# Earphone-1.net
KiCad netlist of a schematic drawn in Altium Designer
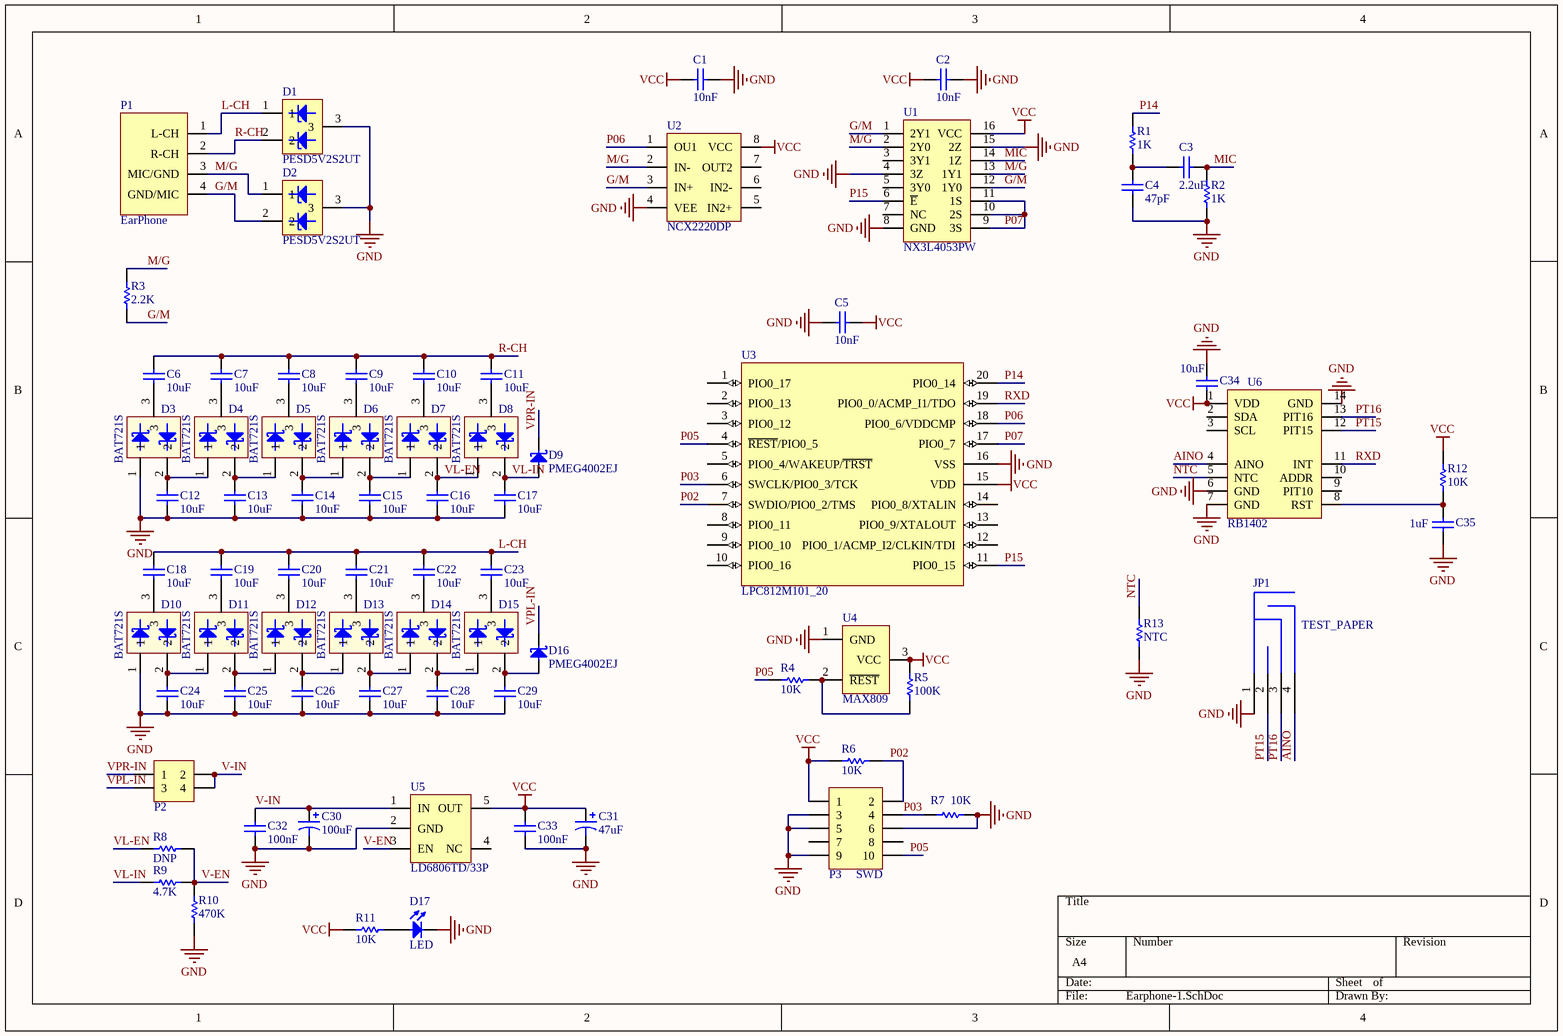
[diagram p0: Earphone-1.SchDoc]

(export (version "E")
  (design (tool "Eeschema 10.0.6"))
  (components
    (comp (ref "C1") (value "10nF") (footprint "0402C") (libsource (lib "Schlib1") (part "CAP")))
    (comp (ref "C2") (value "10nF") (footprint "0402C") (libsource (lib "Schlib1") (part "CAP")))
    (comp (ref "C3") (value "2.2uF") (footprint "0402C") (libsource (lib "Schlib1") (part "CAP")))
    (comp (ref "C4") (value "47pF") (footprint "0402C") (libsource (lib "Schlib1") (part "CAP")))
    (comp (ref "C5") (value "10nF") (footprint "0402C") (libsource (lib "Schlib1") (part "CAP")))
    (comp (ref "C6") (value "10uF") (footprint "0402C") (libsource (lib "Schlib1") (part "CAP")))
    (comp (ref "C7") (value "10uF") (footprint "0402C") (libsource (lib "Schlib1") (part "CAP")))
    (comp (ref "C8") (value "10uF") (footprint "0402C") (libsource (lib "Schlib1") (part "CAP")))
    (comp (ref "C9") (value "10uF") (footprint "0402C") (libsource (lib "Schlib1") (part "CAP")))
    (comp (ref "C10") (value "10uF") (footprint "0402C") (libsource (lib "Schlib1") (part "CAP")))
    (comp (ref "C11") (value "10uF") (footprint "0402C") (libsource (lib "Schlib1") (part "CAP")))
    (comp (ref "C12") (value "10uF") (footprint "0402C") (libsource (lib "Schlib1") (part "CAP")))
    (comp (ref "C13") (value "10uF") (footprint "0402C") (libsource (lib "Schlib1") (part "CAP")))
    (comp (ref "C14") (value "10uF") (footprint "0402C") (libsource (lib "Schlib1") (part "CAP")))
    (comp (ref "C15") (value "10uF") (footprint "0402C") (libsource (lib "Schlib1") (part "CAP")))
    (comp (ref "C16") (value "10uF") (footprint "0402C") (libsource (lib "Schlib1") (part "CAP")))
    (comp (ref "C17") (value "10uF") (footprint "0402C") (libsource (lib "Schlib1") (part "CAP")))
    (comp (ref "C18") (value "10uF") (footprint "0402C") (libsource (lib "Schlib1") (part "CAP")))
    (comp (ref "C19") (value "10uF") (footprint "0402C") (libsource (lib "Schlib1") (part "CAP")))
    (comp (ref "C20") (value "10uF") (footprint "0402C") (libsource (lib "Schlib1") (part "CAP")))
    (comp (ref "C21") (value "10uF") (footprint "0402C") (libsource (lib "Schlib1") (part "CAP")))
    (comp (ref "C22") (value "10uF") (footprint "0402C") (libsource (lib "Schlib1") (part "CAP")))
    (comp (ref "C23") (value "10uF") (footprint "0402C") (libsource (lib "Schlib1") (part "CAP")))
    (comp (ref "C24") (value "10uF") (footprint "0402C") (libsource (lib "Schlib1") (part "CAP")))
    (comp (ref "C25") (value "10uF") (footprint "0402C") (libsource (lib "Schlib1") (part "CAP")))
    (comp (ref "C26") (value "10uF") (footprint "0402C") (libsource (lib "Schlib1") (part "CAP")))
    (comp (ref "C27") (value "10uF") (footprint "0402C") (libsource (lib "Schlib1") (part "CAP")))
    (comp (ref "C28") (value "10uF") (footprint "0402C") (libsource (lib "Schlib1") (part "CAP")))
    (comp (ref "C29") (value "10uF") (footprint "0402C") (libsource (lib "Schlib1") (part "CAP")))
    (comp (ref "C30") (value "100uF") (footprint "T3216-18[A]") (libsource (lib "Schlib1") (part "CAP POL2")))
    (comp (ref "C31") (value "47uF") (footprint "T3216-18[A]") (libsource (lib "Schlib1") (part "CAP POL2")))
    (comp (ref "C32") (value "100nF") (footprint "0402C") (libsource (lib "Schlib1") (part "CAP")))
    (comp (ref "C33") (value "100nF") (footprint "0402C") (libsource (lib "Schlib1") (part "CAP")))
    (comp (ref "C34") (value "10uF") (footprint "0402C") (libsource (lib "Schlib1") (part "CAP")))
    (comp (ref "C35") (value "1uF") (footprint "0402C") (libsource (lib "Schlib1") (part "CAP")))
    (comp (ref "D1")
      (value "PESD5V2S2UT")
      (footprint "SOT23")
      (description "SOT23")
      (libsource (lib "Schlib1") (part "PESD5V2S2UT"))
    )
    (comp (ref "D2")
      (value "PESD5V2S2UT")
      (footprint "SOT23")
      (description "SOT23")
      (libsource (lib "Schlib1") (part "PESD5V2S2UT"))
    )
    (comp (ref "D3")
      (value "BAT721S")
      (footprint "SOT23")
      (description "SOT23")
      (libsource (lib "Schlib1") (part "BAT721S"))
    )
    (comp (ref "D4")
      (value "BAT721S")
      (footprint "SOT23")
      (description "SOT23")
      (libsource (lib "Schlib1") (part "BAT721S"))
    )
    (comp (ref "D5")
      (value "BAT721S")
      (footprint "SOT23")
      (description "SOT23")
      (libsource (lib "Schlib1") (part "BAT721S"))
    )
    (comp (ref "D6")
      (value "BAT721S")
      (footprint "SOT23")
      (description "SOT23")
      (libsource (lib "Schlib1") (part "BAT721S"))
    )
    (comp (ref "D7")
      (value "BAT721S")
      (footprint "SOT23")
      (description "SOT23")
      (libsource (lib "Schlib1") (part "BAT721S"))
    )
    (comp (ref "D8")
      (value "BAT721S")
      (footprint "SOT23")
      (description "SOT23")
      (libsource (lib "Schlib1") (part "BAT721S"))
    )
    (comp (ref "D9")
      (value "PMEG4002EJ")
      (footprint "SOD323")
      (description "SOD323F")
      (libsource (lib "Schlib1") (part "PMEG4002EJ"))
    )
    (comp (ref "D10")
      (value "BAT721S")
      (footprint "SOT23")
      (description "SOT23")
      (libsource (lib "Schlib1") (part "BAT721S"))
    )
    (comp (ref "D11")
      (value "BAT721S")
      (footprint "SOT23")
      (description "SOT23")
      (libsource (lib "Schlib1") (part "BAT721S"))
    )
    (comp (ref "D12")
      (value "BAT721S")
      (footprint "SOT23")
      (description "SOT23")
      (libsource (lib "Schlib1") (part "BAT721S"))
    )
    (comp (ref "D13")
      (value "BAT721S")
      (footprint "SOT23")
      (description "SOT23")
      (libsource (lib "Schlib1") (part "BAT721S"))
    )
    (comp (ref "D14")
      (value "BAT721S")
      (footprint "SOT23")
      (description "SOT23")
      (libsource (lib "Schlib1") (part "BAT721S"))
    )
    (comp (ref "D15")
      (value "BAT721S")
      (footprint "SOT23")
      (description "SOT23")
      (libsource (lib "Schlib1") (part "BAT721S"))
    )
    (comp (ref "D16")
      (value "PMEG4002EJ")
      (footprint "SOD323")
      (description "SOD323F")
      (libsource (lib "Schlib1") (part "PMEG4002EJ"))
    )
    (comp (ref "D17") (value "LED") (footprint "0603L") (libsource (lib "Schlib1") (part "LED")))
    (comp (ref "JP1")
      (value "TEST_PAPER")
      (footprint "TEST_PAPER")
      (libsource (lib "Schlib1") (part "TEST_PAPER"))
    )
    (comp (ref "P1") (value "EarPhone") (footprint "EarPhone") (libsource (lib "Schlib1") (part "EarPhone")))
    (comp (ref "P2")
      (value "Header-2X2")
      (footprint "header-2x2(2.54)")
      (libsource (lib "Schlib1") (part "Header-2X2"))
    )
    (comp (ref "P3")
      (value "SWD")
      (footprint "header-2x5(2.54)")
      (libsource (lib "Schlib1") (part "Header-2X5"))
    )
    (comp (ref "R1") (value "1K") (footprint "0402R") (libsource (lib "Schlib1") (part "RES")))
    (comp (ref "R2") (value "1K") (footprint "0402R") (libsource (lib "Schlib1") (part "RES")))
    (comp (ref "R3") (value "2.2K") (footprint "0402R") (libsource (lib "Schlib1") (part "RES")))
    (comp (ref "R4") (value "10K") (footprint "0402R") (libsource (lib "Schlib1") (part "RES")))
    (comp (ref "R5") (value "100K") (footprint "0402R") (libsource (lib "Schlib1") (part "RES")))
    (comp (ref "R6") (value "10K") (footprint "0402R") (libsource (lib "Schlib1") (part "RES")))
    (comp (ref "R7") (value "10K") (footprint "0402R") (libsource (lib "Schlib1") (part "RES")))
    (comp (ref "R8") (value "DNP") (footprint "0402R") (libsource (lib "Schlib1") (part "RES")))
    (comp (ref "R9") (value "4.7K") (footprint "0402R") (libsource (lib "Schlib1") (part "RES")))
    (comp (ref "R10") (value "470K") (footprint "0402R") (libsource (lib "Schlib1") (part "RES")))
    (comp (ref "R11") (value "10K") (footprint "0402R") (libsource (lib "Schlib1") (part "RES")))
    (comp (ref "R12") (value "10K") (footprint "0402R") (libsource (lib "Schlib1") (part "RES")))
    (comp (ref "R13") (value "NTC") (footprint "0603R") (libsource (lib "Schlib1") (part "RES")))
    (comp (ref "U1")
      (value "NX3L4053PW")
      (footprint "TSSOP16")
      (description "TSSOP16(SOT403-1)")
      (libsource (lib "Schlib1") (part "NX3L4053PW"))
    )
    (comp (ref "U2")
      (value "NCX2220DP")
      (footprint "TSSOP8")
      (description "TSSOP8(SOT505-2)")
      (libsource (lib "Schlib1") (part "NCX2220DP"))
    )
    (comp (ref "U3")
      (value "LPC812M101_20")
      (footprint "TSSOP20")
      (description "TSSOP20")
      (libsource (lib "Schlib1") (part "LPC812M101_20"))
    )
    (comp (ref "U4")
      (value "MAX809")
      (footprint "SOT23")
      (description "SOT23")
      (libsource (lib "Schlib1") (part "MAX809"))
    )
    (comp (ref "U5")
      (value "LD6806TD/33P")
      (footprint "SOT753 (TSOP5)")
      (description "TSOP5(SOT753)")
      (libsource (lib "Schlib1") (part "LD6806TD/33P"))
    )
    (comp (ref "U6") (value "RB1402") (footprint "RB1402") (libsource (lib "Schlib1") (part "RB1402")))
  )
  (nets
    (net (code "1") (name "/AINO") (class "Default")
      (node (ref "JP1") (pin "4") (pinfunction "P_4") (pintype "passive"))
      (node (ref "U6") (pin "4") (pinfunction "AINO_4") (pintype "passive"))
    )
    (net (code "2") (name "/G{slash}M") (class "Default")
      (node (ref "D2") (pin "2") (pinfunction "2_2") (pintype "passive"))
      (node (ref "P1") (pin "4") (pinfunction "GND/MIC_4") (pintype "passive"))
      (node (ref "R3") (pin "1") (pinfunction "1_1") (pintype "passive"))
      (node (ref "U1") (pin "1") (pinfunction "2Y1_1") (pintype "passive"))
      (node (ref "U1") (pin "12") (pinfunction "1Y0_12") (pintype "passive"))
      (node (ref "U2") (pin "3") (pinfunction "IN+_3") (pintype "passive"))
    )
    (net (code "3") (name "/L-CH") (class "Default")
      (node (ref "C18") (pin "2") (pinfunction "2_2") (pintype "passive"))
      (node (ref "C19") (pin "2") (pinfunction "2_2") (pintype "passive"))
      (node (ref "C20") (pin "2") (pinfunction "2_2") (pintype "passive"))
      (node (ref "C21") (pin "2") (pinfunction "2_2") (pintype "passive"))
      (node (ref "C22") (pin "2") (pinfunction "2_2") (pintype "passive"))
      (node (ref "C23") (pin "2") (pinfunction "2_2") (pintype "passive"))
      (node (ref "D1") (pin "1") (pinfunction "1_1") (pintype "passive"))
      (node (ref "P1") (pin "1") (pinfunction "L-CH_1") (pintype "passive"))
    )
    (net (code "4") (name "/MIC") (class "Default")
      (node (ref "C3") (pin "1") (pinfunction "1_1") (pintype "passive"))
      (node (ref "R2") (pin "1") (pinfunction "1_1") (pintype "passive"))
      (node (ref "U1") (pin "14") (pinfunction "1Z_14") (pintype "passive"))
    )
    (net (code "5") (name "/M{slash}G") (class "Default")
      (node (ref "D2") (pin "1") (pinfunction "1_1") (pintype "passive"))
      (node (ref "P1") (pin "3") (pinfunction "MIC/GND_3") (pintype "passive"))
      (node (ref "R3") (pin "2") (pinfunction "2_2") (pintype "passive"))
      (node (ref "U1") (pin "13") (pinfunction "1Y1_13") (pintype "passive"))
      (node (ref "U1") (pin "2") (pinfunction "2Y0_2") (pintype "passive"))
      (node (ref "U2") (pin "2") (pinfunction "IN-_2") (pintype "passive"))
    )
    (net (code "6") (name "/NTC") (class "Default")
      (node (ref "R13") (pin "2") (pinfunction "2_2") (pintype "passive"))
      (node (ref "U6") (pin "5") (pinfunction "NTC_5") (pintype "passive"))
    )
    (net (code "7") (name "/P02") (class "Default")
      (node (ref "P3") (pin "2") (pinfunction "2_2") (pintype "passive"))
      (node (ref "R6") (pin "2") (pinfunction "2_2") (pintype "passive"))
      (node (ref "U3") (pin "7") (pinfunction "SWDIO/PIO0_2/TMS_7") (pintype "bidirectional"))
    )
    (net (code "8") (name "/P03") (class "Default")
      (node (ref "P3") (pin "4") (pinfunction "4_4") (pintype "passive"))
      (node (ref "R7") (pin "1") (pinfunction "1_1") (pintype "passive"))
      (node (ref "U3") (pin "6") (pinfunction "SWCLK/PIO0_3/TCK_6") (pintype "bidirectional"))
    )
    (net (code "9") (name "/P05") (class "Default")
      (node (ref "P3") (pin "10") (pinfunction "10_10") (pintype "passive"))
      (node (ref "R4") (pin "1") (pinfunction "1_1") (pintype "passive"))
      (node (ref "U3") (pin "4") (pinfunction "~{REST}/PIO0_5_4") (pintype "bidirectional"))
    )
    (net (code "10") (name "/P06") (class "Default")
      (node (ref "U2") (pin "1") (pinfunction "OU1_1") (pintype "passive"))
      (node (ref "U3") (pin "18") (pinfunction "PIO0_6/VDDCMP_18") (pintype "bidirectional"))
    )
    (net (code "11") (name "/P07") (class "Default")
      (node (ref "U1") (pin "10") (pinfunction "2S_10") (pintype "passive"))
      (node (ref "U1") (pin "11") (pinfunction "1S_11") (pintype "passive"))
      (node (ref "U1") (pin "9") (pinfunction "3S_9") (pintype "passive"))
      (node (ref "U3") (pin "17") (pinfunction "PIO0_7_17") (pintype "bidirectional"))
    )
    (net (code "12") (name "/P14") (class "Default")
      (node (ref "R1") (pin "1") (pinfunction "1_1") (pintype "passive"))
      (node (ref "U3") (pin "20") (pinfunction "PIO0_14_20") (pintype "bidirectional"))
    )
    (net (code "13") (name "/P15") (class "Default")
      (node (ref "U1") (pin "6") (pinfunction "~{E}_6") (pintype "passive"))
      (node (ref "U3") (pin "11") (pinfunction "PIO0_15_11") (pintype "bidirectional"))
    )
    (net (code "14") (name "/PT15") (class "Default")
      (node (ref "JP1") (pin "2") (pinfunction "PC10_2") (pintype "passive"))
      (node (ref "U6") (pin "12") (pinfunction "PIT15_12") (pintype "passive"))
    )
    (net (code "15") (name "/PT16") (class "Default")
      (node (ref "JP1") (pin "3") (pinfunction "NOP_3") (pintype "passive"))
      (node (ref "U6") (pin "13") (pinfunction "PIT16_13") (pintype "passive"))
    )
    (net (code "16") (name "/R-CH") (class "Default")
      (node (ref "C10") (pin "2") (pinfunction "2_2") (pintype "passive"))
      (node (ref "C11") (pin "2") (pinfunction "2_2") (pintype "passive"))
      (node (ref "C6") (pin "2") (pinfunction "2_2") (pintype "passive"))
      (node (ref "C7") (pin "2") (pinfunction "2_2") (pintype "passive"))
      (node (ref "C8") (pin "2") (pinfunction "2_2") (pintype "passive"))
      (node (ref "C9") (pin "2") (pinfunction "2_2") (pintype "passive"))
      (node (ref "D1") (pin "2") (pinfunction "2_2") (pintype "passive"))
      (node (ref "P1") (pin "2") (pinfunction "R-CH_2") (pintype "passive"))
    )
    (net (code "17") (name "/RXD") (class "Default")
      (node (ref "U3") (pin "19") (pinfunction "PIO0_0/ACMP_I1/TDO_19") (pintype "bidirectional"))
      (node (ref "U6") (pin "11") (pinfunction "INT_11") (pintype "passive"))
    )
    (net (code "18") (name "/V-EN") (class "Default")
      (node (ref "R10") (pin "2") (pinfunction "2_2") (pintype "passive"))
      (node (ref "R8") (pin "2") (pinfunction "2_2") (pintype "passive"))
      (node (ref "R9") (pin "2") (pinfunction "2_2") (pintype "passive"))
      (node (ref "U5") (pin "3") (pinfunction "EN_3") (pintype "passive"))
    )
    (net (code "19") (name "/V-IN") (class "Default")
      (node (ref "C30") (pin "1") (pinfunction "1_1") (pintype "passive"))
      (node (ref "C32") (pin "2") (pinfunction "2_2") (pintype "passive"))
      (node (ref "P2") (pin "2") (pinfunction "2_2") (pintype "passive"))
      (node (ref "P2") (pin "4") (pinfunction "4_4") (pintype "passive"))
      (node (ref "U5") (pin "1") (pinfunction "IN_1") (pintype "passive"))
    )
    (net (code "20") (name "/VL-EN") (class "Default")
      (node (ref "C16") (pin "2") (pinfunction "2_2") (pintype "passive"))
      (node (ref "D7") (pin "2") (pinfunction "2_2") (pintype "passive"))
      (node (ref "D8") (pin "1") (pinfunction "1_1") (pintype "passive"))
      (node (ref "R8") (pin "1") (pinfunction "1_1") (pintype "passive"))
    )
    (net (code "21") (name "/VL-IN") (class "Default")
      (node (ref "C17") (pin "2") (pinfunction "2_2") (pintype "passive"))
      (node (ref "D8") (pin "2") (pinfunction "2_2") (pintype "passive"))
      (node (ref "D9") (pin "2") (pinfunction "2_2") (pintype "passive"))
      (node (ref "R9") (pin "1") (pinfunction "1_1") (pintype "passive"))
    )
    (net (code "22") (name "/VPL-IN") (class "Default")
      (node (ref "D16") (pin "1") (pinfunction "1_1") (pintype "passive"))
      (node (ref "P2") (pin "3") (pinfunction "3_3") (pintype "passive"))
    )
    (net (code "23") (name "/VPR-IN") (class "Default")
      (node (ref "D9") (pin "1") (pinfunction "1_1") (pintype "passive"))
      (node (ref "P2") (pin "1") (pinfunction "1_1") (pintype "passive"))
    )
    (net (code "24") (name "GND") (class "Default")
      (node (ref "C1") (pin "1") (pinfunction "1_1") (pintype "passive"))
      (node (ref "C12") (pin "1") (pinfunction "1_1") (pintype "passive"))
      (node (ref "C13") (pin "1") (pinfunction "1_1") (pintype "passive"))
      (node (ref "C14") (pin "1") (pinfunction "1_1") (pintype "passive"))
      (node (ref "C15") (pin "1") (pinfunction "1_1") (pintype "passive"))
      (node (ref "C16") (pin "1") (pinfunction "1_1") (pintype "passive"))
      (node (ref "C17") (pin "1") (pinfunction "1_1") (pintype "passive"))
      (node (ref "C2") (pin "2") (pinfunction "2_2") (pintype "passive"))
      (node (ref "C24") (pin "1") (pinfunction "1_1") (pintype "passive"))
      (node (ref "C25") (pin "1") (pinfunction "1_1") (pintype "passive"))
      (node (ref "C26") (pin "1") (pinfunction "1_1") (pintype "passive"))
      (node (ref "C27") (pin "1") (pinfunction "1_1") (pintype "passive"))
      (node (ref "C28") (pin "1") (pinfunction "1_1") (pintype "passive"))
      (node (ref "C29") (pin "1") (pinfunction "1_1") (pintype "passive"))
      (node (ref "C30") (pin "2") (pinfunction "2_2") (pintype "passive"))
      (node (ref "C31") (pin "2") (pinfunction "2_2") (pintype "passive"))
      (node (ref "C32") (pin "1") (pinfunction "1_1") (pintype "passive"))
      (node (ref "C33") (pin "1") (pinfunction "1_1") (pintype "passive"))
      (node (ref "C34") (pin "2") (pinfunction "2_2") (pintype "passive"))
      (node (ref "C35") (pin "1") (pinfunction "1_1") (pintype "passive"))
      (node (ref "C4") (pin "1") (pinfunction "1_1") (pintype "passive"))
      (node (ref "C5") (pin "1") (pinfunction "1_1") (pintype "passive"))
      (node (ref "D1") (pin "3") (pinfunction "3_3") (pintype "passive"))
      (node (ref "D10") (pin "1") (pinfunction "1_1") (pintype "passive"))
      (node (ref "D17") (pin "2") (pinfunction "K_2") (pintype "passive"))
      (node (ref "D2") (pin "3") (pinfunction "3_3") (pintype "passive"))
      (node (ref "D3") (pin "1") (pinfunction "1_1") (pintype "passive"))
      (node (ref "JP1") (pin "1") (pinfunction "N_1") (pintype "passive"))
      (node (ref "P3") (pin "3") (pinfunction "3_3") (pintype "passive"))
      (node (ref "P3") (pin "5") (pinfunction "5_5") (pintype "passive"))
      (node (ref "P3") (pin "6") (pinfunction "6_6") (pintype "passive"))
      (node (ref "P3") (pin "9") (pinfunction "9_9") (pintype "passive"))
      (node (ref "R10") (pin "1") (pinfunction "1_1") (pintype "passive"))
      (node (ref "R13") (pin "1") (pinfunction "1_1") (pintype "passive"))
      (node (ref "R2") (pin "2") (pinfunction "2_2") (pintype "passive"))
      (node (ref "R7") (pin "2") (pinfunction "2_2") (pintype "passive"))
      (node (ref "U1") (pin "15") (pinfunction "2Z_15") (pintype "passive"))
      (node (ref "U1") (pin "4") (pinfunction "3Z_4") (pintype "passive"))
      (node (ref "U1") (pin "8") (pinfunction "GND_8") (pintype "passive"))
      (node (ref "U2") (pin "4") (pinfunction "VEE_4") (pintype "passive"))
      (node (ref "U3") (pin "16") (pinfunction "VSS_16") (pintype "passive"))
      (node (ref "U4") (pin "1") (pinfunction "GND_1") (pintype "passive"))
      (node (ref "U5") (pin "2") (pinfunction "GND_2") (pintype "passive"))
      (node (ref "U6") (pin "14") (pinfunction "GND_14") (pintype "passive"))
      (node (ref "U6") (pin "6") (pinfunction "GND_6") (pintype "passive"))
      (node (ref "U6") (pin "7") (pinfunction "GND_7") (pintype "passive"))
    )
    (net (code "25") (name "Net-(C3-Pad2)") (class "Default")
      (node (ref "C3") (pin "2") (pinfunction "2_2") (pintype "passive"))
      (node (ref "C4") (pin "2") (pinfunction "2_2") (pintype "passive"))
      (node (ref "R1") (pin "2") (pinfunction "2_2") (pintype "passive"))
    )
    (net (code "26") (name "Net-(C6-Pad1)") (class "Default")
      (node (ref "C6") (pin "1") (pinfunction "1_1") (pintype "passive"))
      (node (ref "D3") (pin "3") (pinfunction "3_3") (pintype "passive"))
    )
    (net (code "27") (name "Net-(C7-Pad1)") (class "Default")
      (node (ref "C7") (pin "1") (pinfunction "1_1") (pintype "passive"))
      (node (ref "D4") (pin "3") (pinfunction "3_3") (pintype "passive"))
    )
    (net (code "28") (name "Net-(C8-Pad1)") (class "Default")
      (node (ref "C8") (pin "1") (pinfunction "1_1") (pintype "passive"))
      (node (ref "D5") (pin "3") (pinfunction "3_3") (pintype "passive"))
    )
    (net (code "29") (name "Net-(C9-Pad1)") (class "Default")
      (node (ref "C9") (pin "1") (pinfunction "1_1") (pintype "passive"))
      (node (ref "D6") (pin "3") (pinfunction "3_3") (pintype "passive"))
    )
    (net (code "30") (name "Net-(C10-Pad1)") (class "Default")
      (node (ref "C10") (pin "1") (pinfunction "1_1") (pintype "passive"))
      (node (ref "D7") (pin "3") (pinfunction "3_3") (pintype "passive"))
    )
    (net (code "31") (name "Net-(C11-Pad1)") (class "Default")
      (node (ref "C11") (pin "1") (pinfunction "1_1") (pintype "passive"))
      (node (ref "D8") (pin "3") (pinfunction "3_3") (pintype "passive"))
    )
    (net (code "32") (name "Net-(C12-Pad2)") (class "Default")
      (node (ref "C12") (pin "2") (pinfunction "2_2") (pintype "passive"))
      (node (ref "D3") (pin "2") (pinfunction "2_2") (pintype "passive"))
      (node (ref "D4") (pin "1") (pinfunction "1_1") (pintype "passive"))
    )
    (net (code "33") (name "Net-(C13-Pad2)") (class "Default")
      (node (ref "C13") (pin "2") (pinfunction "2_2") (pintype "passive"))
      (node (ref "D4") (pin "2") (pinfunction "2_2") (pintype "passive"))
      (node (ref "D5") (pin "1") (pinfunction "1_1") (pintype "passive"))
    )
    (net (code "34") (name "Net-(C14-Pad2)") (class "Default")
      (node (ref "C14") (pin "2") (pinfunction "2_2") (pintype "passive"))
      (node (ref "D5") (pin "2") (pinfunction "2_2") (pintype "passive"))
      (node (ref "D6") (pin "1") (pinfunction "1_1") (pintype "passive"))
    )
    (net (code "35") (name "Net-(C15-Pad2)") (class "Default")
      (node (ref "C15") (pin "2") (pinfunction "2_2") (pintype "passive"))
      (node (ref "D6") (pin "2") (pinfunction "2_2") (pintype "passive"))
      (node (ref "D7") (pin "1") (pinfunction "1_1") (pintype "passive"))
    )
    (net (code "36") (name "Net-(C18-Pad1)") (class "Default")
      (node (ref "C18") (pin "1") (pinfunction "1_1") (pintype "passive"))
      (node (ref "D10") (pin "3") (pinfunction "3_3") (pintype "passive"))
    )
    (net (code "37") (name "Net-(C19-Pad1)") (class "Default")
      (node (ref "C19") (pin "1") (pinfunction "1_1") (pintype "passive"))
      (node (ref "D11") (pin "3") (pinfunction "3_3") (pintype "passive"))
    )
    (net (code "38") (name "Net-(C20-Pad1)") (class "Default")
      (node (ref "C20") (pin "1") (pinfunction "1_1") (pintype "passive"))
      (node (ref "D12") (pin "3") (pinfunction "3_3") (pintype "passive"))
    )
    (net (code "39") (name "Net-(C21-Pad1)") (class "Default")
      (node (ref "C21") (pin "1") (pinfunction "1_1") (pintype "passive"))
      (node (ref "D13") (pin "3") (pinfunction "3_3") (pintype "passive"))
    )
    (net (code "40") (name "Net-(C22-Pad1)") (class "Default")
      (node (ref "C22") (pin "1") (pinfunction "1_1") (pintype "passive"))
      (node (ref "D14") (pin "3") (pinfunction "3_3") (pintype "passive"))
    )
    (net (code "41") (name "Net-(C23-Pad1)") (class "Default")
      (node (ref "C23") (pin "1") (pinfunction "1_1") (pintype "passive"))
      (node (ref "D15") (pin "3") (pinfunction "3_3") (pintype "passive"))
    )
    (net (code "42") (name "Net-(C24-Pad2)") (class "Default")
      (node (ref "C24") (pin "2") (pinfunction "2_2") (pintype "passive"))
      (node (ref "D10") (pin "2") (pinfunction "2_2") (pintype "passive"))
      (node (ref "D11") (pin "1") (pinfunction "1_1") (pintype "passive"))
    )
    (net (code "43") (name "Net-(C25-Pad2)") (class "Default")
      (node (ref "C25") (pin "2") (pinfunction "2_2") (pintype "passive"))
      (node (ref "D11") (pin "2") (pinfunction "2_2") (pintype "passive"))
      (node (ref "D12") (pin "1") (pinfunction "1_1") (pintype "passive"))
    )
    (net (code "44") (name "Net-(C26-Pad2)") (class "Default")
      (node (ref "C26") (pin "2") (pinfunction "2_2") (pintype "passive"))
      (node (ref "D12") (pin "2") (pinfunction "2_2") (pintype "passive"))
      (node (ref "D13") (pin "1") (pinfunction "1_1") (pintype "passive"))
    )
    (net (code "45") (name "Net-(C27-Pad2)") (class "Default")
      (node (ref "C27") (pin "2") (pinfunction "2_2") (pintype "passive"))
      (node (ref "D13") (pin "2") (pinfunction "2_2") (pintype "passive"))
      (node (ref "D14") (pin "1") (pinfunction "1_1") (pintype "passive"))
    )
    (net (code "46") (name "Net-(C28-Pad2)") (class "Default")
      (node (ref "C28") (pin "2") (pinfunction "2_2") (pintype "passive"))
      (node (ref "D14") (pin "2") (pinfunction "2_2") (pintype "passive"))
      (node (ref "D15") (pin "1") (pinfunction "1_1") (pintype "passive"))
    )
    (net (code "47") (name "Net-(C29-Pad2)") (class "Default")
      (node (ref "C29") (pin "2") (pinfunction "2_2") (pintype "passive"))
      (node (ref "D15") (pin "2") (pinfunction "2_2") (pintype "passive"))
      (node (ref "D16") (pin "2") (pinfunction "2_2") (pintype "passive"))
    )
    (net (code "48") (name "Net-(D17-A)") (class "Default")
      (node (ref "D17") (pin "1") (pinfunction "A_1") (pintype "passive"))
      (node (ref "R11") (pin "2") (pinfunction "2_2") (pintype "passive"))
    )
    (net (code "49") (name "Net-(U4-~{REST})") (class "Default")
      (node (ref "R4") (pin "2") (pinfunction "2_2") (pintype "passive"))
      (node (ref "R5") (pin "1") (pinfunction "1_1") (pintype "passive"))
      (node (ref "U4") (pin "2") (pinfunction "~{REST}_2") (pintype "passive"))
    )
    (net (code "50") (name "Net-(U6-RST)") (class "Default")
      (node (ref "C35") (pin "2") (pinfunction "2_2") (pintype "passive"))
      (node (ref "R12") (pin "1") (pinfunction "1_1") (pintype "passive"))
      (node (ref "U6") (pin "8") (pinfunction "RST_8") (pintype "passive"))
    )
    (net (code "51") (name "VCC") (class "Default")
      (node (ref "C1") (pin "2") (pinfunction "2_2") (pintype "passive"))
      (node (ref "C2") (pin "1") (pinfunction "1_1") (pintype "passive"))
      (node (ref "C31") (pin "1") (pinfunction "1_1") (pintype "passive"))
      (node (ref "C33") (pin "2") (pinfunction "2_2") (pintype "passive"))
      (node (ref "C34") (pin "1") (pinfunction "1_1") (pintype "passive"))
      (node (ref "C5") (pin "2") (pinfunction "2_2") (pintype "passive"))
      (node (ref "P3") (pin "1") (pinfunction "1_1") (pintype "passive"))
      (node (ref "R11") (pin "1") (pinfunction "1_1") (pintype "passive"))
      (node (ref "R12") (pin "2") (pinfunction "2_2") (pintype "passive"))
      (node (ref "R5") (pin "2") (pinfunction "2_2") (pintype "passive"))
      (node (ref "R6") (pin "1") (pinfunction "1_1") (pintype "passive"))
      (node (ref "U1") (pin "16") (pinfunction "VCC_16") (pintype "passive"))
      (node (ref "U2") (pin "8") (pinfunction "VCC_8") (pintype "passive"))
      (node (ref "U3") (pin "15") (pinfunction "VDD_15") (pintype "passive"))
      (node (ref "U4") (pin "3") (pinfunction "VCC_3") (pintype "passive"))
      (node (ref "U5") (pin "5") (pinfunction "OUT_5") (pintype "passive"))
      (node (ref "U6") (pin "1") (pinfunction "VDD_1") (pintype "passive"))
    )
    (net (code "52") (name "unconnected-(P3-Pad7)") (class "Default")
      (node (ref "P3") (pin "7") (pinfunction "7_7") (pintype "passive"))
    )
    (net (code "53") (name "unconnected-(P3-Pad8)") (class "Default")
      (node (ref "P3") (pin "8") (pinfunction "8_8") (pintype "passive"))
    )
    (net (code "54") (name "unconnected-(U1-3Y0-Pad5)") (class "Default")
      (node (ref "U1") (pin "5") (pinfunction "3Y0_5") (pintype "passive"))
    )
    (net (code "55") (name "unconnected-(U1-3Y1-Pad3)") (class "Default")
      (node (ref "U1") (pin "3") (pinfunction "3Y1_3") (pintype "passive"))
    )
    (net (code "56") (name "unconnected-(U1-NC-Pad7)") (class "Default")
      (node (ref "U1") (pin "7") (pinfunction "NC_7") (pintype "passive"))
    )
    (net (code "57") (name "unconnected-(U2-IN2+-Pad5)") (class "Default")
      (node (ref "U2") (pin "5") (pinfunction "IN2+_5") (pintype "passive"))
    )
    (net (code "58") (name "unconnected-(U2-IN2--Pad6)") (class "Default")
      (node (ref "U2") (pin "6") (pinfunction "IN2-_6") (pintype "passive"))
    )
    (net (code "59") (name "unconnected-(U2-OUT2-Pad7)") (class "Default")
      (node (ref "U2") (pin "7") (pinfunction "OUT2_7") (pintype "passive"))
    )
    (net (code "60") (name "unconnected-(U3-PIO0_1{slash}ACMP_I2{slash}CLKIN{slash}TDI-Pad12)") (class "Default")
      (node (ref "U3") (pin "12") (pinfunction "PIO0_1/ACMP_I2/CLKIN/TDI_12") (pintype "bidirectional"))
    )
    (net (code "61") (name "unconnected-(U3-PIO0_4{slash}WAKEUP{slash}~{TRST}-Pad5)") (class "Default")
      (node (ref "U3") (pin "5") (pinfunction "PIO0_4/WAKEUP/~{TRST}_5") (pintype "bidirectional"))
    )
    (net (code "62") (name "unconnected-(U3-PIO0_8{slash}XTALIN-Pad14)") (class "Default")
      (node (ref "U3") (pin "14") (pinfunction "PIO0_8/XTALIN_14") (pintype "bidirectional"))
    )
    (net (code "63") (name "unconnected-(U3-PIO0_9{slash}XTALOUT-Pad13)") (class "Default")
      (node (ref "U3") (pin "13") (pinfunction "PIO0_9/XTALOUT_13") (pintype "bidirectional"))
    )
    (net (code "64") (name "unconnected-(U3-PIO0_10-Pad9)") (class "Default")
      (node (ref "U3") (pin "9") (pinfunction "PIO0_10_9") (pintype "bidirectional"))
    )
    (net (code "65") (name "unconnected-(U3-PIO0_11-Pad8)") (class "Default")
      (node (ref "U3") (pin "8") (pinfunction "PIO0_11_8") (pintype "bidirectional"))
    )
    (net (code "66") (name "unconnected-(U3-PIO0_12-Pad3)") (class "Default")
      (node (ref "U3") (pin "3") (pinfunction "PIO0_12_3") (pintype "bidirectional"))
    )
    (net (code "67") (name "unconnected-(U3-PIO0_13-Pad2)") (class "Default")
      (node (ref "U3") (pin "2") (pinfunction "PIO0_13_2") (pintype "bidirectional"))
    )
    (net (code "68") (name "unconnected-(U3-PIO0_16-Pad10)") (class "Default")
      (node (ref "U3") (pin "10") (pinfunction "PIO0_16_10") (pintype "bidirectional"))
    )
    (net (code "69") (name "unconnected-(U3-PIO0_17-Pad1)") (class "Default")
      (node (ref "U3") (pin "1") (pinfunction "PIO0_17_1") (pintype "bidirectional"))
    )
    (net (code "70") (name "unconnected-(U5-NC-Pad4)") (class "Default")
      (node (ref "U5") (pin "4") (pinfunction "NC_4") (pintype "passive"))
    )
    (net (code "71") (name "unconnected-(U6-ADDR-Pad10)") (class "Default")
      (node (ref "U6") (pin "10") (pinfunction "ADDR_10") (pintype "passive"))
    )
    (net (code "72") (name "unconnected-(U6-PIT10-Pad9)") (class "Default")
      (node (ref "U6") (pin "9") (pinfunction "PIT10_9") (pintype "passive"))
    )
    (net (code "73") (name "unconnected-(U6-SCL-Pad3)") (class "Default")
      (node (ref "U6") (pin "3") (pinfunction "SCL_3") (pintype "passive"))
    )
    (net (code "74") (name "unconnected-(U6-SDA-Pad2)") (class "Default")
      (node (ref "U6") (pin "2") (pinfunction "SDA_2") (pintype "passive"))
    )
  )
)
